# TC264Power.net
KiCad netlist of a schematic drawn in Altium Designer
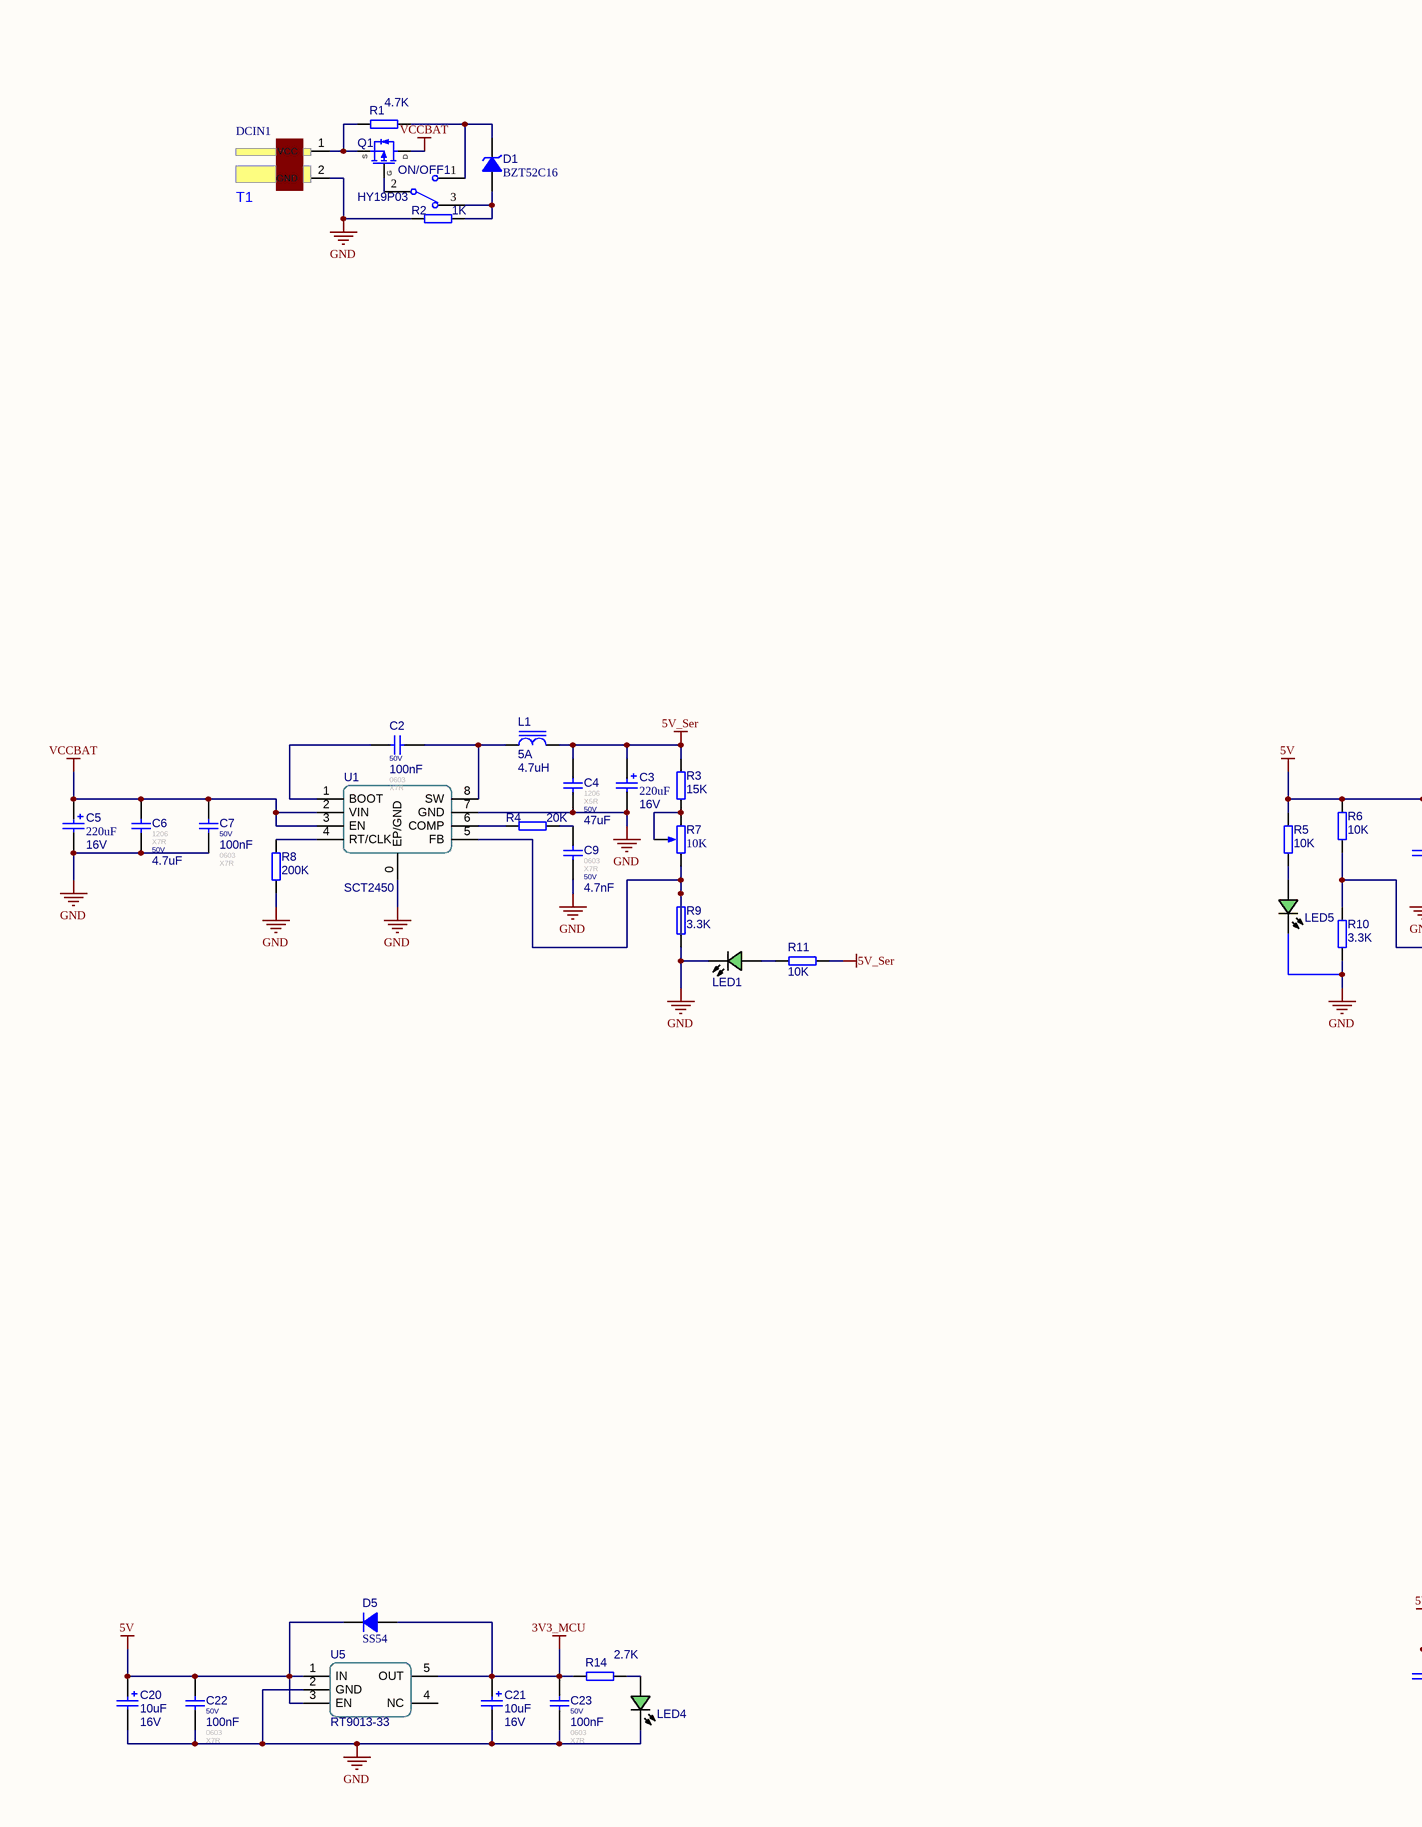
[diagram p0: TC264Power.SchDoc, left]
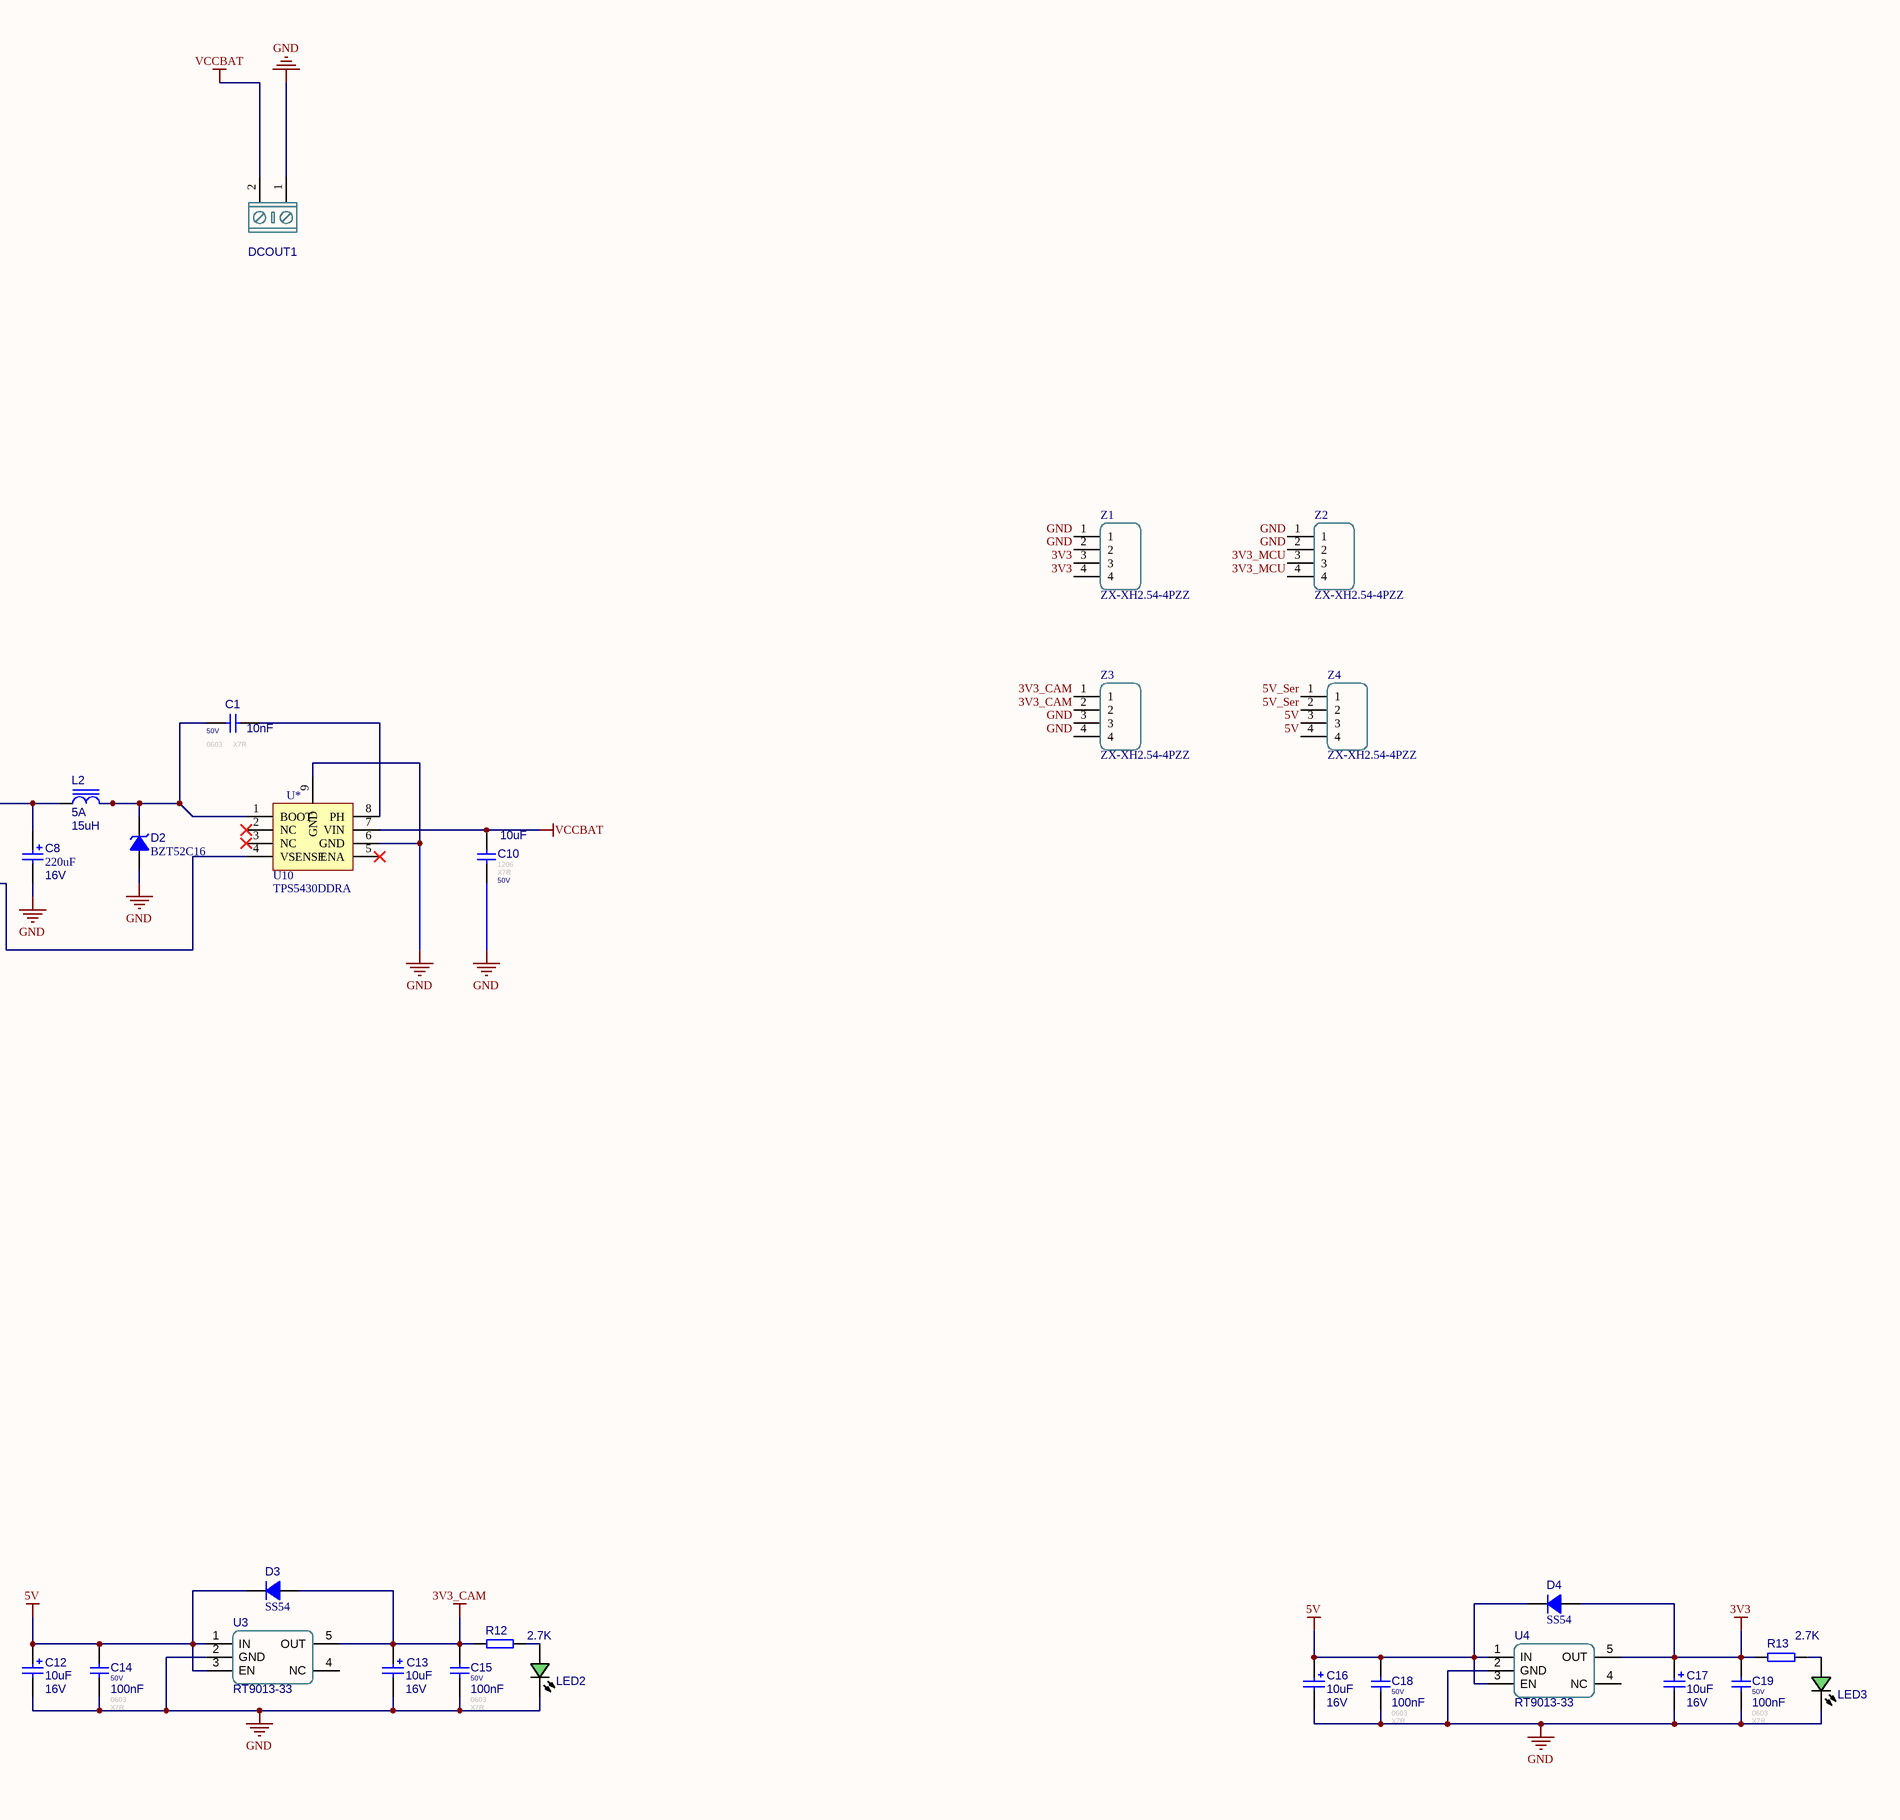
[diagram p1: TC264Power.SchDoc, right]

(export (version "E")
  (design (tool "Eeschema 10.0.6"))
  (components
    (comp (ref "C1")
      (value "10nF")
      (footprint "0603")
      (description "贴片电容")
      (fields
        (field (name "VOLTAGE") "50V")
        (field (name "TOLERANCE") "±10%")
        (field (name "TYPE") "X7R")
        (field (name "Comment") "10nF ±10% 50V")
      )
      (libsource (lib "TC264") (part "Cap-Chip"))
    )
    (comp (ref "C2")
      (value "100nF")
      (footprint "0603")
      (description "贴片电容")
      (fields
        (field (name "VOLTAGE") "50V")
        (field (name "TOLERANCE") "±10%")
        (field (name "TYPE") "X7R")
        (field (name "Comment") "100nF ±10% 50V")
      )
      (libsource (lib "TC264") (part "Cap-Chip"))
    )
    (comp (ref "C3")
      (value "220uF")
      (footprint "CAPS6.3")
      (description "Polarized Capacitor (Radial)")
      (fields
        (field (name "VOLTAGE") "16V")
        (field (name "Comment") "220uF 16V")
        (field (name "PUBLISHER") "Altium Limited")
      )
      (libsource (lib "TC264") (part "Cap-Solid_1"))
    )
    (comp (ref "C4")
      (value "47uF")
      (footprint "1206")
      (description "贴片电容")
      (fields
        (field (name "TOLERANCE") "±10%")
        (field (name "TYPE") "X5R")
        (field (name "VOLTAGE") "50V")
        (field (name "Comment") "47uF ±10% 50V")
      )
      (libsource (lib "TC264") (part "Cap-Chip_2"))
    )
    (comp (ref "C5")
      (value "220uF")
      (footprint "CAPS6.3")
      (description "Polarized Capacitor (Radial)")
      (fields
        (field (name "VOLTAGE") "16V")
        (field (name "Comment") "220uF 16V")
        (field (name "PUBLISHER") "Altium Limited")
      )
      (libsource (lib "TC264") (part "Cap-Solid_1"))
    )
    (comp (ref "C6")
      (value "4.7uF")
      (footprint "1206")
      (description "贴片电容")
      (fields
        (field (name "TOLERANCE") "±10%")
        (field (name "TYPE") "X7R")
        (field (name "VOLTAGE") "50V")
        (field (name "Comment") "4.7uF ±10% 50V")
      )
      (libsource (lib "TC264") (part "Cap-Chip_1"))
    )
    (comp (ref "C7")
      (value "100nF")
      (footprint "0603")
      (description "贴片电容")
      (fields
        (field (name "VOLTAGE") "50V")
        (field (name "TOLERANCE") "±10%")
        (field (name "TYPE") "X7R")
        (field (name "Comment") "100nF ±10% 50V")
      )
      (libsource (lib "TC264") (part "Cap-Chip"))
    )
    (comp (ref "C8")
      (value "220uF")
      (footprint "CAPS6.3")
      (description "Polarized Capacitor (Radial)")
      (fields
        (field (name "VOLTAGE") "16V")
        (field (name "Comment") "220uF 16V")
        (field (name "PUBLISHER") "Altium Limited")
      )
      (libsource (lib "TC264") (part "Cap-Solid_1"))
    )
    (comp (ref "C9")
      (value "4.7nF")
      (footprint "0603")
      (description "贴片电容")
      (fields
        (field (name "TOLERANCE") "±10%")
        (field (name "TYPE") "X7R")
        (field (name "VOLTAGE") "50V")
        (field (name "Comment") "4.7nF ±10% 50V")
      )
      (libsource (lib "TC264") (part "Cap-Chip_3"))
    )
    (comp (ref "C10")
      (value "10uF")
      (footprint "1206")
      (description "贴片电容")
      (fields
        (field (name "TOLERANCE") "±10%")
        (field (name "TYPE") "X7R")
        (field (name "VOLTAGE") "50V")
        (field (name "Comment") "10uF ±10% 50V")
      )
      (libsource (lib "TC264") (part "Cap-Chip_1"))
    )
    (comp (ref "C12")
      (value "10uF")
      (footprint "CAPT3216")
      (description "Tantalum Capacitor")
      (fields
        (field (name "VOLTAGE") "16V")
        (field (name "Comment") "10uF 16V")
        (field (name "PUBLISHER") "Altium Limited")
      )
      (libsource (lib "TC264") (part "Cap-Tan"))
    )
    (comp (ref "C13")
      (value "10uF")
      (footprint "CAPT3216")
      (description "Tantalum Capacitor")
      (fields
        (field (name "VOLTAGE") "16V")
        (field (name "Comment") "10uF 16V")
        (field (name "PUBLISHER") "Altium Limited")
      )
      (libsource (lib "TC264") (part "Cap-Tan"))
    )
    (comp (ref "C14")
      (value "100nF")
      (footprint "0603")
      (description "贴片电容")
      (fields
        (field (name "TOLERANCE") "±10%")
        (field (name "VOLTAGE") "50V")
        (field (name "TYPE") "X7R")
        (field (name "Comment") "100nF ±10% 50V")
      )
      (libsource (lib "TC264") (part "Cap-Chip"))
    )
    (comp (ref "C15")
      (value "100nF")
      (footprint "0603")
      (description "贴片电容")
      (fields
        (field (name "TOLERANCE") "±10%")
        (field (name "VOLTAGE") "50V")
        (field (name "TYPE") "X7R")
        (field (name "Comment") "100nF ±10% 50V")
      )
      (libsource (lib "TC264") (part "Cap-Chip"))
    )
    (comp (ref "C16")
      (value "10uF")
      (footprint "CAPT3216")
      (description "Tantalum Capacitor")
      (fields
        (field (name "VOLTAGE") "16V")
        (field (name "Comment") "10uF 16V")
        (field (name "PUBLISHER") "Altium Limited")
      )
      (libsource (lib "TC264") (part "Cap-Tan"))
    )
    (comp (ref "C17")
      (value "10uF")
      (footprint "CAPT3216")
      (description "Tantalum Capacitor")
      (fields
        (field (name "VOLTAGE") "16V")
        (field (name "Comment") "10uF 16V")
        (field (name "PUBLISHER") "Altium Limited")
      )
      (libsource (lib "TC264") (part "Cap-Tan"))
    )
    (comp (ref "C18")
      (value "100nF")
      (footprint "0603")
      (description "贴片电容")
      (fields
        (field (name "TOLERANCE") "±10%")
        (field (name "VOLTAGE") "50V")
        (field (name "TYPE") "X7R")
        (field (name "Comment") "100nF ±10% 50V")
      )
      (libsource (lib "TC264") (part "Cap-Chip"))
    )
    (comp (ref "C19")
      (value "100nF")
      (footprint "0603")
      (description "贴片电容")
      (fields
        (field (name "TOLERANCE") "±10%")
        (field (name "VOLTAGE") "50V")
        (field (name "TYPE") "X7R")
        (field (name "Comment") "100nF ±10% 50V")
      )
      (libsource (lib "TC264") (part "Cap-Chip"))
    )
    (comp (ref "C20")
      (value "10uF")
      (footprint "CAPT3216")
      (description "Tantalum Capacitor")
      (fields
        (field (name "VOLTAGE") "16V")
        (field (name "Comment") "10uF 16V")
        (field (name "PUBLISHER") "Altium Limited")
      )
      (libsource (lib "TC264") (part "Cap-Tan"))
    )
    (comp (ref "C21")
      (value "10uF")
      (footprint "CAPT3216")
      (description "Tantalum Capacitor")
      (fields
        (field (name "VOLTAGE") "16V")
        (field (name "Comment") "10uF 16V")
        (field (name "PUBLISHER") "Altium Limited")
      )
      (libsource (lib "TC264") (part "Cap-Tan"))
    )
    (comp (ref "C22")
      (value "100nF")
      (footprint "0603")
      (description "贴片电容")
      (fields
        (field (name "TOLERANCE") "±10%")
        (field (name "VOLTAGE") "50V")
        (field (name "TYPE") "X7R")
        (field (name "Comment") "100nF ±10% 50V")
      )
      (libsource (lib "TC264") (part "Cap-Chip"))
    )
    (comp (ref "C23")
      (value "100nF")
      (footprint "0603")
      (description "贴片电容")
      (fields
        (field (name "TOLERANCE") "±10%")
        (field (name "VOLTAGE") "50V")
        (field (name "TYPE") "X7R")
        (field (name "Comment") "100nF ±10% 50V")
      )
      (libsource (lib "TC264") (part "Cap-Chip"))
    )
    (comp (ref "D1")
      (value "BZT52C16")
      (footprint "SOD-123-L")
      (description "TRANSIENT VOLTAGE  SUPPRESSOR DIODE")
      (fields (field (name "PUBLISHER") "Altium Limited"))
      (libsource (lib "TC264") (part "Diode TVS Uni-Dir"))
    )
    (comp (ref "D2")
      (value "BZT52C16")
      (footprint "SOD-123-L")
      (description "TRANSIENT VOLTAGE  SUPPRESSOR DIODE")
      (fields (field (name "PUBLISHER") "Altium Limited"))
      (libsource (lib "TC264") (part "Diode TVS Uni-Dir"))
    )
    (comp (ref "D3")
      (value "SS54")
      (footprint "SMA[DO-214AC]")
      (description "普通二极管 Diode")
      (fields (field (name "PUBLISHER") "Altium Limited"))
      (libsource (lib "TC264") (part "Diode"))
    )
    (comp (ref "D4")
      (value "SS54")
      (footprint "SMA[DO-214AC]")
      (description "普通二极管 Diode")
      (fields (field (name "PUBLISHER") "Altium Limited"))
      (libsource (lib "TC264") (part "Diode"))
    )
    (comp (ref "D5")
      (value "SS54")
      (footprint "SMA[DO-214AC]")
      (description "普通二极管 Diode")
      (fields (field (name "PUBLISHER") "Altium Limited"))
      (libsource (lib "TC264") (part "Diode"))
    )
    (comp (ref "DCIN1")
      (value "T1")
      (footprint "Wired T-Header ThroughHole")
      (description "T型插头")
      (libsource (lib "TC264") (part "T_Header"))
    )
    (comp (ref "DCOUT1")
      (value "KF/WJ/DG 30x connecter")
      (footprint "KF/WJ/DG 301-2p-5.0mm")
      (description "接线端子 2Pin")
      (libsource (lib "TC264") (part "KF/WJ/DG 30x"))
    )
    (comp (ref "L1")
      (value "4.7uH")
      (footprint "0630 TPC 7*7*3")
      (description "功率电感")
      (fields
        (field (name "IMAX") "5A")
        (field (name "Comment") "4.7uH 5A")
        (field (name "PUBLISHER") "Altium Limited")
      )
      (libsource (lib "TC264") (part "Ind-Power"))
    )
    (comp (ref "L2")
      (value "15uH")
      (footprint "0630 TPC 7*7*3")
      (description "功率电感")
      (fields
        (field (name "IMAX") "5A")
        (field (name "Comment") "15uH 5A")
        (field (name "PUBLISHER") "Altium Limited")
      )
      (libsource (lib "TC264") (part "Ind-Power"))
    )
    (comp (ref "LED1")
      (value "翠绿贴片LED")
      (footprint "LEDC1608(0603)")
      (fields (field (name "PUBLISHER") "Altium Limited"))
      (libsource (lib "TC264") (part "LED Chip Green"))
    )
    (comp (ref "LED2")
      (value "翠绿贴片LED")
      (footprint "LEDC1608(0603)")
      (fields (field (name "PUBLISHER") "Altium Limited"))
      (libsource (lib "TC264") (part "LED Chip Green"))
    )
    (comp (ref "LED3")
      (value "翠绿贴片LED")
      (footprint "LEDC1608(0603)")
      (fields (field (name "PUBLISHER") "Altium Limited"))
      (libsource (lib "TC264") (part "LED Chip Green"))
    )
    (comp (ref "LED4")
      (value "翠绿贴片LED")
      (footprint "LEDC1608(0603)")
      (fields (field (name "PUBLISHER") "Altium Limited"))
      (libsource (lib "TC264") (part "LED Chip Green"))
    )
    (comp (ref "LED5")
      (value "翠绿贴片LED")
      (footprint "LEDC1608(0603)")
      (fields (field (name "PUBLISHER") "Altium Limited"))
      (libsource (lib "TC264") (part "LED Chip Green"))
    )
    (comp (ref "ON/OFF1")
      (value "SW-SPDT")
      (footprint "SS12D10")
      (description "单刀双掷开关 3脚船型、钮子、拨动开关 SPDT Subminiature Toggle Switch")
      (fields (field (name "PUBLISHER") "Altium Limited"))
      (libsource (lib "TC264") (part "SW-SPDT"))
    )
    (comp (ref "Q1")
      (value "HY19P03")
      (footprint "TO-252AA")
      (description "HY19P03 P-Channel MOSFET")
      (libsource (lib "TC264") (part "HY19P03"))
    )
    (comp (ref "R1")
      (value "4.7K")
      (footprint "RESC1608[0603]S-N")
      (description "贴片电阻")
      (fields (field (name "TOLERANCE") "±1%") (field (name "Comment") "4.7K ±1%"))
      (libsource (lib "TC264") (part "Res-Chip_4"))
    )
    (comp (ref "R2")
      (value "1K")
      (footprint "RESC1608[0603]S-N")
      (description "贴片电阻")
      (fields (field (name "TOLERANCE") "±1%") (field (name "Comment") "1K ±1%"))
      (libsource (lib "TC264") (part "Res-Chip_3"))
    )
    (comp (ref "R3")
      (value "15K")
      (footprint "RESC1608[0603]S-N")
      (description "贴片电阻")
      (fields (field (name "TOLERANCE") "±1%") (field (name "Comment") "15K ±1%"))
      (libsource (lib "TC264") (part "Res-Chip_7"))
    )
    (comp (ref "R4")
      (value "20K")
      (footprint "RESC1608[0603]S-N")
      (description "贴片电阻")
      (fields (field (name "TOLERANCE") "±1%") (field (name "Comment") "20K ±1%"))
      (libsource (lib "TC264") (part "Res-Chip_6"))
    )
    (comp (ref "R5")
      (value "10K")
      (footprint "RESC1608[0603]S-N")
      (description "贴片电阻")
      (fields (field (name "TOLERANCE") "±1%") (field (name "Comment") "10K ±1%"))
      (libsource (lib "TC264") (part "Res-Chip"))
    )
    (comp (ref "R6")
      (value "10K")
      (footprint "RESC1608[0603]S-N")
      (description "贴片电阻")
      (fields (field (name "TOLERANCE") "±1%") (field (name "Comment") "10K ±1%"))
      (libsource (lib "TC264") (part "Res-Chip"))
    )
    (comp (ref "R7")
      (value "10K")
      (footprint "RESPOT3296")
      (description "可调电阻")
      (libsource (lib "TC264") (part "Res-Adj-3p"))
    )
    (comp (ref "R8")
      (value "200K")
      (footprint "RESC1608[0603]S-N")
      (description "贴片电阻")
      (fields (field (name "TOLERANCE") "±1%") (field (name "Comment") "200K ±1%"))
      (libsource (lib "TC264") (part "Res-Chip_5"))
    )
    (comp (ref "R9")
      (value "3.3K")
      (footprint "RESC1608[0603]S-N")
      (description "贴片电阻")
      (fields (field (name "TOLERANCE") "±1%") (field (name "Comment") "3.3K ±1%"))
      (libsource (lib "TC264") (part "Res-Chip_8"))
    )
    (comp (ref "R10")
      (value "3.3K")
      (footprint "RESC1608[0603]S-N")
      (description "贴片电阻")
      (fields (field (name "TOLERANCE") "±1%") (field (name "Comment") "3.3K ±1%"))
      (libsource (lib "TC264") (part "Res-Chip_8"))
    )
    (comp (ref "R11")
      (value "10K")
      (footprint "RESC1608[0603]S-N")
      (description "贴片电阻")
      (fields (field (name "TOLERANCE") "±1%") (field (name "Comment") "10K ±1%"))
      (libsource (lib "TC264") (part "Res-Chip"))
    )
    (comp (ref "R12")
      (value "2.7K")
      (footprint "RESC1608[0603]S-N")
      (description "贴片电阻")
      (fields (field (name "TOLERANCE") "±1%") (field (name "Comment") "2.7K ±1%"))
      (libsource (lib "TC264") (part "Res-Chip_2"))
    )
    (comp (ref "R13")
      (value "2.7K")
      (footprint "RESC1608[0603]S-N")
      (description "贴片电阻")
      (fields (field (name "TOLERANCE") "±1%") (field (name "Comment") "2.7K ±1%"))
      (libsource (lib "TC264") (part "Res-Chip_2"))
    )
    (comp (ref "R14")
      (value "2.7K")
      (footprint "RESC1608[0603]S-N")
      (description "贴片电阻")
      (fields (field (name "TOLERANCE") "±1%") (field (name "Comment") "2.7K ±1%"))
      (libsource (lib "TC264") (part "Res-Chip_2"))
    )
    (comp (ref "U1") (value "SCT2450") (footprint "SOP-8E") (libsource (lib "TC264") (part "SCT2450")))
    (comp (ref "U3")
      (value "RT9013-33")
      (footprint "SOT-23-5")
      (description "3.3V 500mA SOT-23-5 LDO")
      (libsource (lib "TC264") (part "RT9013-33"))
    )
    (comp (ref "U4")
      (value "RT9013-33")
      (footprint "SOT-23-5")
      (description "3.3V 500mA SOT-23-5 LDO")
      (libsource (lib "TC264") (part "RT9013-33"))
    )
    (comp (ref "U5")
      (value "RT9013-33")
      (footprint "SOT-23-5")
      (description "3.3V 500mA SOT-23-5 LDO")
      (libsource (lib "TC264") (part "RT9013-33"))
    )
    (comp (ref "U10")
      (value "TPS5430DDRA")
      (footprint "TC264:SOP8-1R27-3R90")
      (libsource (lib "TC264") (part "TPS5430DDRA"))
    )
    (comp (ref "Z1")
      (value "ZX-XH2.54-4PZZ")
      (footprint "ZX-XH2.54-4PZZ")
      (description "接线端子")
      (libsource (lib "TangCW") (part "ZX-XH2.54-4PZZ"))
    )
    (comp (ref "Z2")
      (value "ZX-XH2.54-4PZZ")
      (footprint "ZX-XH2.54-4PZZ")
      (description "接线端子")
      (libsource (lib "TangCW") (part "ZX-XH2.54-4PZZ"))
    )
    (comp (ref "Z3")
      (value "ZX-XH2.54-4PZZ")
      (footprint "ZX-XH2.54-4PZZ")
      (description "接线端子")
      (libsource (lib "TangCW") (part "ZX-XH2.54-4PZZ"))
    )
    (comp (ref "Z4")
      (value "ZX-XH2.54-4PZZ")
      (footprint "ZX-XH2.54-4PZZ")
      (description "接线端子")
      (libsource (lib "TangCW") (part "ZX-XH2.54-4PZZ"))
    )
  )
  (nets
    (net (code "1") (name "3V3") (class "Default")
      (node (ref "C17") (pin "1") (pinfunction "1_1") (pintype "passive"))
      (node (ref "C19") (pin "2") (pinfunction "2_2") (pintype "passive"))
      (node (ref "D4") (pin "A") (pinfunction "A_A") (pintype "passive"))
      (node (ref "R13") (pin "1") (pinfunction "1_1") (pintype "passive"))
      (node (ref "U4") (pin "5") (pinfunction "OUT_5") (pintype "passive"))
      (node (ref "Z1") (pin "3") (pinfunction "3_3") (pintype "passive"))
      (node (ref "Z1") (pin "4") (pinfunction "4_4") (pintype "passive"))
    )
    (net (code "2") (name "3V3_CAM") (class "Default")
      (node (ref "C13") (pin "1") (pinfunction "1_1") (pintype "passive"))
      (node (ref "C15") (pin "2") (pinfunction "2_2") (pintype "passive"))
      (node (ref "D3") (pin "A") (pinfunction "A_A") (pintype "passive"))
      (node (ref "R12") (pin "1") (pinfunction "1_1") (pintype "passive"))
      (node (ref "U3") (pin "5") (pinfunction "OUT_5") (pintype "passive"))
      (node (ref "Z3") (pin "1") (pinfunction "1_1") (pintype "passive"))
      (node (ref "Z3") (pin "2") (pinfunction "2_2") (pintype "passive"))
    )
    (net (code "3") (name "3V3_MCU") (class "Default")
      (node (ref "C21") (pin "1") (pinfunction "1_1") (pintype "passive"))
      (node (ref "C23") (pin "2") (pinfunction "2_2") (pintype "passive"))
      (node (ref "D5") (pin "A") (pinfunction "A_A") (pintype "passive"))
      (node (ref "R14") (pin "1") (pinfunction "1_1") (pintype "passive"))
      (node (ref "U5") (pin "5") (pinfunction "OUT_5") (pintype "passive"))
      (node (ref "Z2") (pin "3") (pinfunction "3_3") (pintype "passive"))
      (node (ref "Z2") (pin "4") (pinfunction "4_4") (pintype "passive"))
    )
    (net (code "4") (name "5V") (class "Default")
      (node (ref "C12") (pin "1") (pinfunction "1_1") (pintype "passive"))
      (node (ref "C14") (pin "2") (pinfunction "2_2") (pintype "passive"))
      (node (ref "C16") (pin "1") (pinfunction "1_1") (pintype "passive"))
      (node (ref "C18") (pin "2") (pinfunction "2_2") (pintype "passive"))
      (node (ref "C20") (pin "1") (pinfunction "1_1") (pintype "passive"))
      (node (ref "C22") (pin "2") (pinfunction "2_2") (pintype "passive"))
      (node (ref "C8") (pin "1") (pinfunction "1_1") (pintype "passive"))
      (node (ref "D3") (pin "K") (pinfunction "K_K") (pintype "passive"))
      (node (ref "D4") (pin "K") (pinfunction "K_K") (pintype "passive"))
      (node (ref "D5") (pin "K") (pinfunction "K_K") (pintype "passive"))
      (node (ref "L2") (pin "1") (pinfunction "1_1") (pintype "passive"))
      (node (ref "R5") (pin "2") (pinfunction "2_2") (pintype "passive"))
      (node (ref "R6") (pin "2") (pinfunction "2_2") (pintype "passive"))
      (node (ref "U3") (pin "1") (pinfunction "IN_1") (pintype "passive"))
      (node (ref "U3") (pin "3") (pinfunction "EN_3") (pintype "passive"))
      (node (ref "U4") (pin "1") (pinfunction "IN_1") (pintype "passive"))
      (node (ref "U4") (pin "3") (pinfunction "EN_3") (pintype "passive"))
      (node (ref "U5") (pin "1") (pinfunction "IN_1") (pintype "passive"))
      (node (ref "U5") (pin "3") (pinfunction "EN_3") (pintype "passive"))
      (node (ref "Z4") (pin "3") (pinfunction "3_3") (pintype "passive"))
      (node (ref "Z4") (pin "4") (pinfunction "4_4") (pintype "passive"))
    )
    (net (code "5") (name "5V_Ser") (class "Default")
      (node (ref "C3") (pin "1") (pinfunction "1_1") (pintype "passive"))
      (node (ref "C4") (pin "2") (pinfunction "2_2") (pintype "passive"))
      (node (ref "L1") (pin "2") (pinfunction "2_2") (pintype "passive"))
      (node (ref "R11") (pin "2") (pinfunction "2_2") (pintype "passive"))
      (node (ref "R3") (pin "2") (pinfunction "2_2") (pintype "passive"))
      (node (ref "Z4") (pin "1") (pinfunction "1_1") (pintype "passive"))
      (node (ref "Z4") (pin "2") (pinfunction "2_2") (pintype "passive"))
    )
    (net (code "6") (name "GND") (class "Default")
      (node (ref "C10") (pin "2") (pinfunction "2_2") (pintype "passive"))
      (node (ref "C12") (pin "2") (pinfunction "2_2") (pintype "passive"))
      (node (ref "C13") (pin "2") (pinfunction "2_2") (pintype "passive"))
      (node (ref "C14") (pin "1") (pinfunction "1_1") (pintype "passive"))
      (node (ref "C15") (pin "1") (pinfunction "1_1") (pintype "passive"))
      (node (ref "C16") (pin "2") (pinfunction "2_2") (pintype "passive"))
      (node (ref "C17") (pin "2") (pinfunction "2_2") (pintype "passive"))
      (node (ref "C18") (pin "1") (pinfunction "1_1") (pintype "passive"))
      (node (ref "C19") (pin "1") (pinfunction "1_1") (pintype "passive"))
      (node (ref "C20") (pin "2") (pinfunction "2_2") (pintype "passive"))
      (node (ref "C21") (pin "2") (pinfunction "2_2") (pintype "passive"))
      (node (ref "C22") (pin "1") (pinfunction "1_1") (pintype "passive"))
      (node (ref "C23") (pin "1") (pinfunction "1_1") (pintype "passive"))
      (node (ref "C3") (pin "2") (pinfunction "2_2") (pintype "passive"))
      (node (ref "C4") (pin "1") (pinfunction "1_1") (pintype "passive"))
      (node (ref "C5") (pin "2") (pinfunction "2_2") (pintype "passive"))
      (node (ref "C6") (pin "1") (pinfunction "1_1") (pintype "passive"))
      (node (ref "C7") (pin "1") (pinfunction "1_1") (pintype "passive"))
      (node (ref "C8") (pin "2") (pinfunction "2_2") (pintype "passive"))
      (node (ref "C9") (pin "2") (pinfunction "2_2") (pintype "passive"))
      (node (ref "D2") (pin "A") (pinfunction "A_A") (pintype "passive"))
      (node (ref "DCIN1") (pin "2") (pinfunction "GND_2") (pintype "passive"))
      (node (ref "DCOUT1") (pin "1") (pinfunction "1_1") (pintype "passive"))
      (node (ref "LED1") (pin "C") (pinfunction "C_C") (pintype "passive"))
      (node (ref "LED2") (pin "C") (pinfunction "C_C") (pintype "passive"))
      (node (ref "LED3") (pin "C") (pinfunction "C_C") (pintype "passive"))
      (node (ref "LED4") (pin "C") (pinfunction "C_C") (pintype "passive"))
      (node (ref "LED5") (pin "C") (pinfunction "C_C") (pintype "passive"))
      (node (ref "R10") (pin "2") (pinfunction "2_2") (pintype "passive"))
      (node (ref "R2") (pin "2") (pinfunction "2_2") (pintype "passive"))
      (node (ref "R8") (pin "1") (pinfunction "1_1") (pintype "passive"))
      (node (ref "R9") (pin "2") (pinfunction "2_2") (pintype "passive"))
      (node (ref "U1") (pin "0") (pinfunction "EP/GND_0") (pintype "passive"))
      (node (ref "U1") (pin "7") (pinfunction "GND_7") (pintype "passive"))
      (node (ref "U10") (pin "6") (pinfunction "GND_6") (pintype "passive"))
      (node (ref "U10") (pin "9") (pinfunction "GND_9") (pintype "passive"))
      (node (ref "U3") (pin "2") (pinfunction "GND_2") (pintype "passive"))
      (node (ref "U4") (pin "2") (pinfunction "GND_2") (pintype "passive"))
      (node (ref "U5") (pin "2") (pinfunction "GND_2") (pintype "passive"))
      (node (ref "Z1") (pin "1") (pinfunction "1_1") (pintype "passive"))
      (node (ref "Z1") (pin "2") (pinfunction "2_2") (pintype "passive"))
      (node (ref "Z2") (pin "1") (pinfunction "1_1") (pintype "passive"))
      (node (ref "Z2") (pin "2") (pinfunction "2_2") (pintype "passive"))
      (node (ref "Z3") (pin "3") (pinfunction "3_3") (pintype "passive"))
      (node (ref "Z3") (pin "4") (pinfunction "4_4") (pintype "passive"))
    )
    (net (code "7") (name "Net-(C9-Pad1)") (class "Default")
      (node (ref "C9") (pin "1") (pinfunction "1_1") (pintype "passive"))
      (node (ref "R4") (pin "1") (pinfunction "1_1") (pintype "passive"))
    )
    (net (code "8") (name "Net-(D1-PadA)") (class "Default")
      (node (ref "D1") (pin "A") (pinfunction "A_A") (pintype "passive"))
      (node (ref "ON/OFF1") (pin "3") (pintype "passive"))
      (node (ref "R2") (pin "1") (pinfunction "1_1") (pintype "passive"))
    )
    (net (code "9") (name "Net-(D1-PadK)") (class "Default")
      (node (ref "D1") (pin "K") (pinfunction "K_K") (pintype "passive"))
      (node (ref "ON/OFF1") (pin "1") (pintype "passive"))
      (node (ref "R1") (pin "2") (pinfunction "2_2") (pintype "passive"))
    )
    (net (code "10") (name "Net-(DCIN1-VCC)") (class "Default")
      (node (ref "DCIN1") (pin "1") (pinfunction "VCC_1") (pintype "passive"))
      (node (ref "Q1") (pin "3") (pinfunction "S_3") (pintype "passive"))
      (node (ref "R1") (pin "1") (pinfunction "1_1") (pintype "passive"))
    )
    (net (code "11") (name "Net-(LED1-PadA)") (class "Default")
      (node (ref "LED1") (pin "A") (pinfunction "A_A") (pintype "passive"))
      (node (ref "R11") (pin "1") (pinfunction "1_1") (pintype "passive"))
    )
    (net (code "12") (name "Net-(LED2-PadA)") (class "Default")
      (node (ref "LED2") (pin "A") (pinfunction "A_A") (pintype "passive"))
      (node (ref "R12") (pin "2") (pinfunction "2_2") (pintype "passive"))
    )
    (net (code "13") (name "Net-(LED3-PadA)") (class "Default")
      (node (ref "LED3") (pin "A") (pinfunction "A_A") (pintype "passive"))
      (node (ref "R13") (pin "2") (pinfunction "2_2") (pintype "passive"))
    )
    (net (code "14") (name "Net-(LED4-PadA)") (class "Default")
      (node (ref "LED4") (pin "A") (pinfunction "A_A") (pintype "passive"))
      (node (ref "R14") (pin "2") (pinfunction "2_2") (pintype "passive"))
    )
    (net (code "15") (name "Net-(LED5-PadA)") (class "Default")
      (node (ref "LED5") (pin "A") (pinfunction "A_A") (pintype "passive"))
      (node (ref "R5") (pin "1") (pinfunction "1_1") (pintype "passive"))
    )
    (net (code "16") (name "Net-(Q1-G)") (class "Default")
      (node (ref "ON/OFF1") (pin "2") (pintype "passive"))
      (node (ref "Q1") (pin "2") (pinfunction "G_2") (pintype "passive"))
    )
    (net (code "17") (name "Net-(R7-BOT)") (class "Default")
      (node (ref "R7") (pin "2") (pinfunction "BOT_2") (pintype "passive"))
      (node (ref "R9") (pin "1") (pinfunction "1_1") (pintype "passive"))
      (node (ref "U1") (pin "5") (pinfunction "FB_5") (pintype "passive"))
    )
    (net (code "18") (name "Net-(R7-TOP)") (class "Default")
      (node (ref "R3") (pin "1") (pinfunction "1_1") (pintype "passive"))
      (node (ref "R7") (pin "1") (pinfunction "TOP_1") (pintype "passive"))
      (node (ref "R7") (pin "ADJ") (pinfunction "ADJ_ADJ") (pintype "passive"))
    )
    (net (code "19") (name "Net-(U1-BOOT)") (class "Default")
      (node (ref "C2") (pin "1") (pinfunction "1_1") (pintype "passive"))
      (node (ref "U1") (pin "1") (pinfunction "BOOT_1") (pintype "passive"))
    )
    (net (code "20") (name "Net-(U1-COMP)") (class "Default")
      (node (ref "R4") (pin "2") (pinfunction "2_2") (pintype "passive"))
      (node (ref "U1") (pin "6") (pinfunction "COMP_6") (pintype "passive"))
    )
    (net (code "21") (name "Net-(U1-RT{slash}CLK)") (class "Default")
      (node (ref "R8") (pin "2") (pinfunction "2_2") (pintype "passive"))
      (node (ref "U1") (pin "4") (pinfunction "RT/CLK_4") (pintype "passive"))
    )
    (net (code "22") (name "Net-(U1-SW)") (class "Default")
      (node (ref "C2") (pin "2") (pinfunction "2_2") (pintype "passive"))
      (node (ref "L1") (pin "1") (pinfunction "1_1") (pintype "passive"))
      (node (ref "U1") (pin "8") (pinfunction "SW_8") (pintype "passive"))
    )
    (net (code "23") (name "Net-(U10-BOOT)") (class "Default")
      (node (ref "C1") (pin "1") (pinfunction "1_1") (pintype "passive"))
      (node (ref "D2") (pin "K") (pinfunction "K_K") (pintype "passive"))
      (node (ref "L2") (pin "2") (pinfunction "2_2") (pintype "passive"))
      (node (ref "U10") (pin "1") (pinfunction "BOOT_1") (pintype "passive"))
    )
    (net (code "24") (name "Net-(U10-PH)") (class "Default")
      (node (ref "C1") (pin "2") (pinfunction "2_2") (pintype "passive"))
      (node (ref "U10") (pin "8") (pinfunction "PH_8") (pintype "passive"))
    )
    (net (code "25") (name "Net-(U10-VSENSE)") (class "Default")
      (node (ref "R10") (pin "1") (pinfunction "1_1") (pintype "passive"))
      (node (ref "R6") (pin "1") (pinfunction "1_1") (pintype "passive"))
      (node (ref "U10") (pin "4") (pinfunction "VSENSE_4") (pintype "passive"))
    )
    (net (code "26") (name "VCCBAT") (class "Default")
      (node (ref "C10") (pin "1") (pinfunction "1_1") (pintype "passive"))
      (node (ref "C5") (pin "1") (pinfunction "1_1") (pintype "passive"))
      (node (ref "C6") (pin "2") (pinfunction "2_2") (pintype "passive"))
      (node (ref "C7") (pin "2") (pinfunction "2_2") (pintype "passive"))
      (node (ref "DCOUT1") (pin "2") (pinfunction "2_2") (pintype "passive"))
      (node (ref "Q1") (pin "1") (pinfunction "D_1") (pintype "passive"))
      (node (ref "U1") (pin "2") (pinfunction "VIN_2") (pintype "passive"))
      (node (ref "U1") (pin "3") (pinfunction "EN_3") (pintype "passive"))
      (node (ref "U10") (pin "7") (pinfunction "VIN_7") (pintype "passive"))
    )
    (net (code "27") (name "unconnected-(U3-NC-Pad4)") (class "Default")
      (node (ref "U3") (pin "4") (pinfunction "NC_4") (pintype "passive"))
    )
    (net (code "28") (name "unconnected-(U4-NC-Pad4)") (class "Default")
      (node (ref "U4") (pin "4") (pinfunction "NC_4") (pintype "passive"))
    )
    (net (code "29") (name "unconnected-(U5-NC-Pad4)") (class "Default")
      (node (ref "U5") (pin "4") (pinfunction "NC_4") (pintype "passive"))
    )
    (net (code "30") (name "unconnected-(U10-ENA-Pad5)") (class "Default")
      (node (ref "U10") (pin "5") (pinfunction "ENA_5") (pintype "passive+no_connect"))
    )
    (net (code "31") (name "unconnected-(U10-NC-Pad2)") (class "Default")
      (node (ref "U10") (pin "2") (pinfunction "NC_2") (pintype "passive+no_connect"))
    )
    (net (code "32") (name "unconnected-(U10-NC-Pad3)") (class "Default")
      (node (ref "U10") (pin "3") (pinfunction "NC_3") (pintype "passive+no_connect"))
    )
  )
)
